# TPS560430.net
KiCad netlist of a schematic drawn in Altium Designer
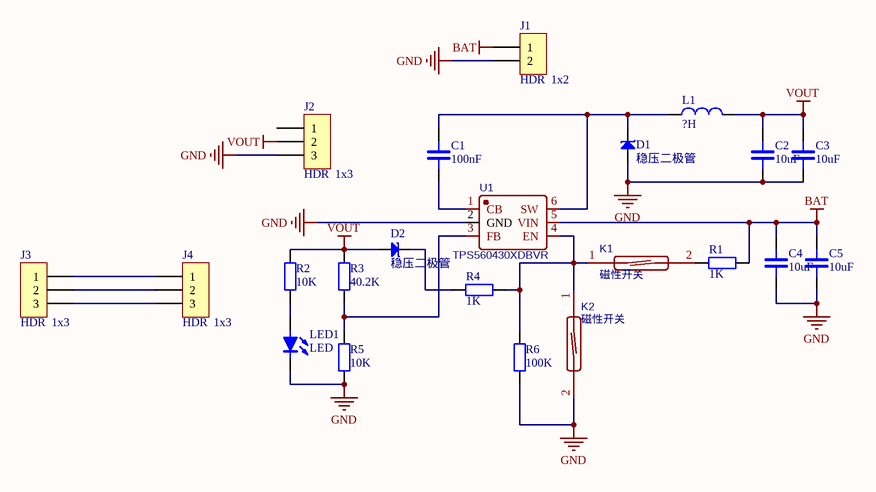
[diagram p0: 飞镖电源TPS560430.SchDoc]

(export (version "E")
  (design (tool "Eeschema 10.0.6"))
  (components
    (comp (ref "C1")
      (value "100nF")
      (footprint "0603_C")
      (description "Capacitor")
      (libsource (lib "General（旧）") (part "CAP"))
    )
    (comp (ref "C2")
      (value "10uF")
      (footprint "1206_C")
      (description "Capacitor")
      (libsource (lib "General（旧）") (part "CAP"))
    )
    (comp (ref "C3")
      (value "10uF")
      (footprint "1206_C")
      (description "Capacitor")
      (libsource (lib "General（旧）") (part "CAP"))
    )
    (comp (ref "C4")
      (value "10uF")
      (footprint "1206_C")
      (description "Capacitor")
      (libsource (lib "General（旧）") (part "CAP"))
    )
    (comp (ref "C5")
      (value "10uF")
      (footprint "1206_C")
      (description "Capacitor")
      (libsource (lib "General（旧）") (part "CAP"))
    )
    (comp (ref "D1") (value "稳压二极管") (footprint "SOD-123") (libsource (lib "General（旧）") (part "稳压二极管")))
    (comp (ref "D2") (value "稳压二极管") (footprint "SOD-123") (libsource (lib "General（旧）") (part "稳压二极管")))
    (comp (ref "J1")
      (value "HDR  1x2")
      (footprint "排针排母 2P 2.54mm")
      (description "Connector")
      (libsource (lib "General（旧）") (part "HDR  1x2"))
    )
    (comp (ref "J2")
      (value "HDR  1x3")
      (footprint "排针排母 3P 2.54mm")
      (description "Connector")
      (libsource (lib "General（旧）") (part "HDR  1x3"))
    )
    (comp (ref "J3")
      (value "HDR  1x3")
      (footprint "排针排母 3P 2.54mm")
      (description "Connector")
      (libsource (lib "") (part "HDR  1x3_1"))
    )
    (comp (ref "J4")
      (value "HDR  1x3")
      (footprint "排针排母 3P 2.54mm")
      (description "Connector")
      (libsource (lib "General（旧）") (part "HDR  1x3"))
    )
    (comp (ref "K1")
      (value "磁性开关")
      (footprint "MKA14103")
      (description "开关")
      (fields
        (field (name "BOM_SUPPLIER PART") "C575284")
        (field (name "BOM_MANUFACTURER PART") "KSK-SME560-1015")
        (field (name "CONTRIBUTOR") "LCSC")
      )
      (libsource (lib "General（旧）") (part "干簧管"))
    )
    (comp (ref "K2")
      (value "磁性开关")
      (footprint "MKA14103")
      (description "开关")
      (fields
        (field (name "BOM_SUPPLIER PART") "C575284")
        (field (name "BOM_MANUFACTURER PART") "KSK-SME560-1015")
        (field (name "CONTRIBUTOR") "LCSC")
      )
      (libsource (lib "General（旧）") (part "干簧管"))
    )
    (comp (ref "L1")
      (value "?H")
      (footprint "SMD_7*7*4MM")
      (description "Inductor")
      (fields (field (name "PUBLISHER") "Altium Limited"))
      (libsource (lib "General（旧）") (part "Inductor"))
    )
    (comp (ref "LED1") (value "LED") (footprint "LED_0603") (libsource (lib "General（旧）") (part "LED")))
    (comp (ref "R1")
      (value "1K")
      (footprint "0603_R")
      (description "Resistor")
      (libsource (lib "General（旧）") (part "RES"))
    )
    (comp (ref "R2")
      (value "10K")
      (footprint "0603_R")
      (description "Resistor")
      (libsource (lib "") (part "RES_1"))
    )
    (comp (ref "R3")
      (value "40.2K")
      (footprint "0603_R")
      (description "Resistor")
      (libsource (lib "") (part "RES_1"))
    )
    (comp (ref "R4")
      (value "1K")
      (footprint "0603_R")
      (description "Resistor")
      (libsource (lib "General（旧）") (part "RES"))
    )
    (comp (ref "R5")
      (value "10K")
      (footprint "0603_R")
      (description "Resistor")
      (libsource (lib "") (part "RES_1"))
    )
    (comp (ref "R6")
      (value "100K")
      (footprint "0603_R")
      (description "Resistor")
      (libsource (lib "") (part "RES_2"))
    )
    (comp (ref "U1")
      (value "TPS560430XDBVR")
      (footprint "SOT-23-6")
      (fields (field (name "BOM_SUPPLIER PART") "C524782") (field (name "CONTRIBUTOR") "LCSC"))
      (libsource (lib "General（旧）") (part "TPS560430XDBVR"))
    )
  )
  (nets
    (net (code "1") (name "BAT") (class "Default")
      (node (ref "C4") (pin "2") (pinfunction "2_2") (pintype "passive"))
      (node (ref "C5") (pin "2") (pinfunction "2_2") (pintype "passive"))
      (node (ref "J1") (pin "1") (pinfunction "1_1") (pintype "passive"))
      (node (ref "R1") (pin "2") (pinfunction "2_2") (pintype "passive"))
      (node (ref "U1") (pin "5") (pinfunction "VIN_5") (pintype "passive"))
    )
    (net (code "2") (name "GND") (class "Default")
      (node (ref "C2") (pin "1") (pinfunction "1_1") (pintype "passive"))
      (node (ref "C3") (pin "1") (pinfunction "1_1") (pintype "passive"))
      (node (ref "C4") (pin "1") (pinfunction "1_1") (pintype "passive"))
      (node (ref "C5") (pin "1") (pinfunction "1_1") (pintype "passive"))
      (node (ref "D1") (pin "1") (pinfunction "A_1") (pintype "passive"))
      (node (ref "J1") (pin "2") (pinfunction "2_2") (pintype "passive"))
      (node (ref "J2") (pin "3") (pinfunction "3_3") (pintype "passive"))
      (node (ref "K2") (pin "2") (pinfunction "2_2") (pintype "passive"))
      (node (ref "LED1") (pin "2") (pinfunction "C_2") (pintype "passive"))
      (node (ref "R5") (pin "1") (pinfunction "1_1") (pintype "passive"))
      (node (ref "R6") (pin "2") (pinfunction "2_2") (pintype "passive"))
      (node (ref "U1") (pin "2") (pinfunction "GND_2") (pintype "passive"))
    )
    (net (code "3") (name "Net-(D1-K)") (class "Default")
      (node (ref "C1") (pin "1") (pinfunction "1_1") (pintype "passive"))
      (node (ref "D1") (pin "2") (pinfunction "K_2") (pintype "passive"))
      (node (ref "L1") (pin "1") (pinfunction "1_1") (pintype "passive"))
      (node (ref "U1") (pin "6") (pinfunction "SW_6") (pintype "passive"))
    )
    (net (code "4") (name "Net-(D2-K)") (class "Default")
      (node (ref "D2") (pin "2") (pinfunction "K_2") (pintype "passive"))
      (node (ref "R4") (pin "1") (pinfunction "1_1") (pintype "passive"))
    )
    (net (code "5") (name "Net-(J3-Pad1)") (class "Default")
      (node (ref "J3") (pin "1") (pinfunction "1_1") (pintype "passive"))
      (node (ref "J4") (pin "1") (pinfunction "1_1") (pintype "passive"))
    )
    (net (code "6") (name "Net-(J3-Pad2)") (class "Default")
      (node (ref "J3") (pin "2") (pinfunction "2_2") (pintype "passive"))
      (node (ref "J4") (pin "2") (pinfunction "2_2") (pintype "passive"))
    )
    (net (code "7") (name "Net-(J3-Pad3)") (class "Default")
      (node (ref "J3") (pin "3") (pinfunction "3_3") (pintype "passive"))
      (node (ref "J4") (pin "3") (pinfunction "3_3") (pintype "passive"))
    )
    (net (code "8") (name "Net-(K1-Pad2)") (class "Default")
      (node (ref "K1") (pin "2") (pinfunction "2_2") (pintype "passive"))
      (node (ref "R1") (pin "1") (pinfunction "1_1") (pintype "passive"))
    )
    (net (code "9") (name "Net-(LED1-A)") (class "Default")
      (node (ref "LED1") (pin "1") (pinfunction "A_1") (pintype "passive"))
      (node (ref "R2") (pin "1") (pinfunction "1_1") (pintype "passive"))
    )
    (net (code "10") (name "Net-(U1-CB)") (class "Default")
      (node (ref "C1") (pin "2") (pinfunction "2_2") (pintype "passive"))
      (node (ref "U1") (pin "1") (pinfunction "CB_1") (pintype "passive"))
    )
    (net (code "11") (name "Net-(U1-EN)") (class "Default")
      (node (ref "K1") (pin "1") (pinfunction "1_1") (pintype "passive"))
      (node (ref "K2") (pin "1") (pinfunction "1_1") (pintype "passive"))
      (node (ref "R4") (pin "2") (pinfunction "2_2") (pintype "passive"))
      (node (ref "R6") (pin "1") (pinfunction "1_1") (pintype "passive"))
      (node (ref "U1") (pin "4") (pinfunction "EN_4") (pintype "passive"))
    )
    (net (code "12") (name "Net-(U1-FB)") (class "Default")
      (node (ref "R3") (pin "1") (pinfunction "1_1") (pintype "passive"))
      (node (ref "R5") (pin "2") (pinfunction "2_2") (pintype "passive"))
      (node (ref "U1") (pin "3") (pinfunction "FB_3") (pintype "passive"))
    )
    (net (code "13") (name "VOUT") (class "Default")
      (node (ref "C2") (pin "2") (pinfunction "2_2") (pintype "passive"))
      (node (ref "C3") (pin "2") (pinfunction "2_2") (pintype "passive"))
      (node (ref "D2") (pin "1") (pinfunction "A_1") (pintype "passive"))
      (node (ref "J2") (pin "2") (pinfunction "2_2") (pintype "passive"))
      (node (ref "L1") (pin "2") (pinfunction "2_2") (pintype "passive"))
      (node (ref "R2") (pin "2") (pinfunction "2_2") (pintype "passive"))
      (node (ref "R3") (pin "2") (pinfunction "2_2") (pintype "passive"))
    )
    (net (code "14") (name "unconnected-(J2-Pad1)") (class "Default")
      (node (ref "J2") (pin "1") (pinfunction "1_1") (pintype "passive"))
    )
  )
)
